# compteur_modifie_essence.net
KiCad netlist of a schematic drawn in EAGLE
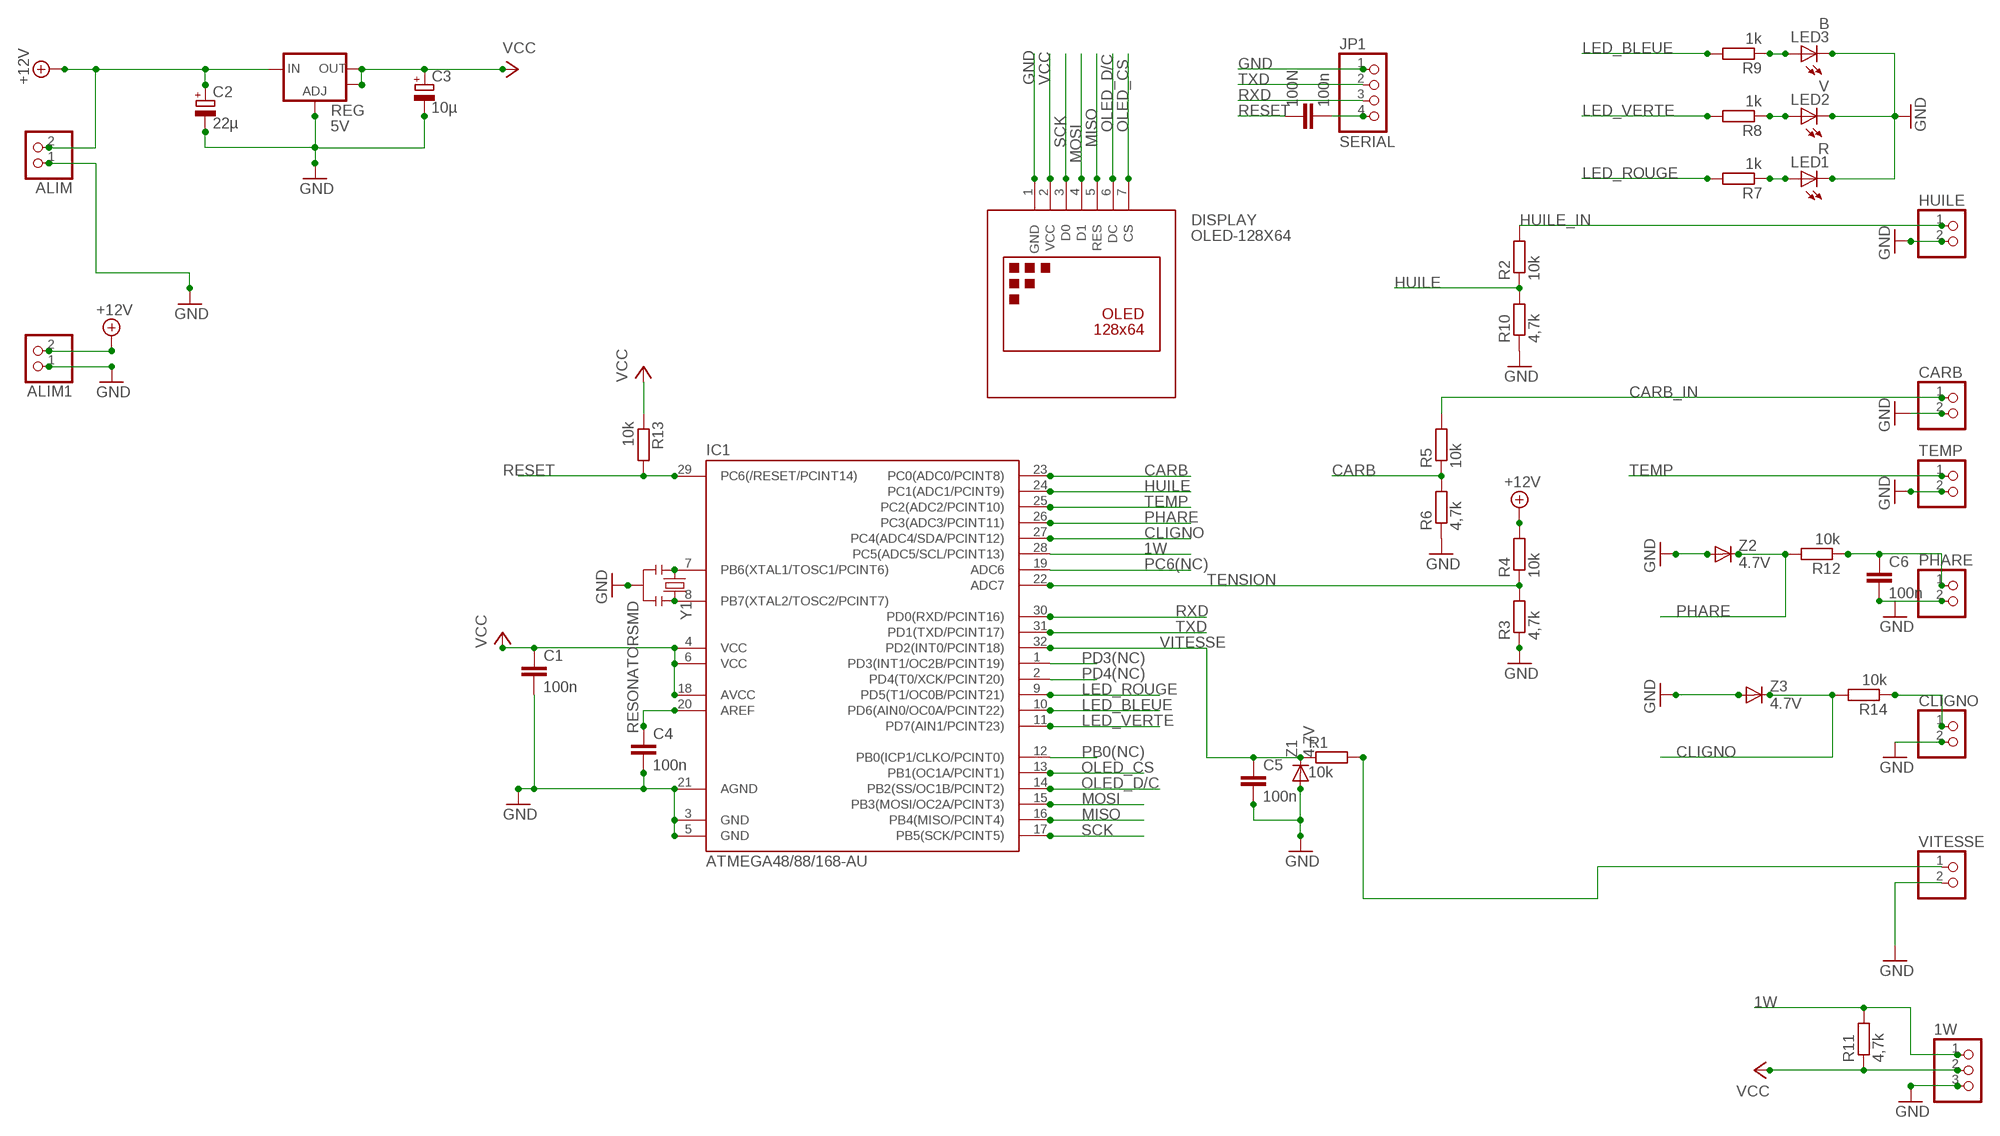
[diagram p0: schematic, sheet 1]

(export (version "E")
  (design (tool "Eeschema 10.0.6"))
  (components
    (comp (ref "1W")
      (value "PINHD-1X3CB")
      (footprint "eagle-import:1X03-CLEANBIG")
      (libsource (lib "eagle-import") (part "PINHD-1X3CB"))
    )
    (comp (ref "100N")
      (value "100n")
      (footprint "eagle-import:C1206")
      (libsource (lib "eagle-import") (part "C-EUC1206"))
    )
    (comp (ref "ALIM")
      (value "PINHD-1X2")
      (footprint "eagle-import:1X02")
      (libsource (lib "eagle-import") (part "PINHD-1X2"))
    )
    (comp (ref "ALIM1")
      (value "PINHD-1X2")
      (footprint "eagle-import:1X02")
      (libsource (lib "eagle-import") (part "PINHD-1X2"))
    )
    (comp (ref "C1")
      (value "100n")
      (footprint "eagle-import:C1206")
      (libsource (lib "eagle-import") (part "C-EUC1206"))
    )
    (comp (ref "C2")
      (value "22µ")
      (footprint "eagle-import:SMC_D")
      (libsource (lib "eagle-import") (part "resistor_CPOL-EUSMCD"))
    )
    (comp (ref "C3")
      (value "10µ")
      (footprint "eagle-import:SMC_C")
      (libsource (lib "eagle-import") (part "CPOL-EUSMCC"))
    )
    (comp (ref "C4")
      (value "100n")
      (footprint "eagle-import:C1206")
      (libsource (lib "eagle-import") (part "C-EUC1206"))
    )
    (comp (ref "C5")
      (value "100n")
      (footprint "eagle-import:C1206")
      (libsource (lib "eagle-import") (part "C-EUC1206"))
    )
    (comp (ref "C6")
      (value "100n")
      (footprint "eagle-import:C1206")
      (libsource (lib "eagle-import") (part "C-EUC1206"))
    )
    (comp (ref "CARB")
      (value "PINHD-1X2")
      (footprint "eagle-import:1X02")
      (libsource (lib "eagle-import") (part "PINHD-1X2"))
    )
    (comp (ref "CLIGNO")
      (value "PINHD-1X2")
      (footprint "eagle-import:1X02")
      (libsource (lib "eagle-import") (part "PINHD-1X2"))
    )
    (comp (ref "DISPLAY")
      (value "OLED-128X64")
      (footprint "eagle-import:DISPLAY-OLED-128X64")
      (libsource (lib "eagle-import") (part "DISPLAY-OLED-128X64"))
    )
    (comp (ref "HUILE")
      (value "PINHD-1X2")
      (footprint "eagle-import:1X02")
      (libsource (lib "eagle-import") (part "PINHD-1X2"))
    )
    (comp (ref "IC1")
      (value "ATMEGA48/88/168-AU")
      (footprint "eagle-import:TQFP32-08")
      (libsource (lib "eagle-import") (part "ATMEGA48/88/168-AU"))
    )
    (comp (ref "JP1")
      (value "SERIAL")
      (footprint "eagle-import:1X04_ROUND")
      (libsource (lib "eagle-import") (part "HEADER-1X4ROUND"))
    )
    (comp (ref "LED1")
      (value "R")
      (footprint "eagle-import:LED5MM")
      (libsource (lib "eagle-import") (part "LED5MM"))
    )
    (comp (ref "LED2")
      (value "V")
      (footprint "eagle-import:LED5MM")
      (libsource (lib "eagle-import") (part "LED5MM"))
    )
    (comp (ref "LED3")
      (value "B")
      (footprint "eagle-import:LED5MM")
      (libsource (lib "eagle-import") (part "LED5MM"))
    )
    (comp (ref "PHARE")
      (value "PINHD-1X2")
      (footprint "eagle-import:1X02")
      (libsource (lib "eagle-import") (part "PINHD-1X2"))
    )
    (comp (ref "R1")
      (value "10k")
      (footprint "eagle-import:R1206")
      (libsource (lib "eagle-import") (part "R-EU_R1206"))
    )
    (comp (ref "R2")
      (value "10k")
      (footprint "eagle-import:R1206")
      (libsource (lib "eagle-import") (part "R-EU_R1206"))
    )
    (comp (ref "R3")
      (value "4,7k")
      (footprint "eagle-import:R1206")
      (libsource (lib "eagle-import") (part "R-EU_R1206"))
    )
    (comp (ref "R4")
      (value "10k")
      (footprint "eagle-import:R1206")
      (libsource (lib "eagle-import") (part "R-EU_R1206"))
    )
    (comp (ref "R5")
      (value "10k")
      (footprint "eagle-import:R1206")
      (libsource (lib "eagle-import") (part "R-EU_R1206"))
    )
    (comp (ref "R6")
      (value "4,7k")
      (footprint "eagle-import:R1206")
      (libsource (lib "eagle-import") (part "R-EU_R1206"))
    )
    (comp (ref "R7")
      (value "1k")
      (footprint "eagle-import:R1206")
      (libsource (lib "eagle-import") (part "R-EU_R1206"))
    )
    (comp (ref "R8")
      (value "1k")
      (footprint "eagle-import:R1206")
      (libsource (lib "eagle-import") (part "R-EU_R1206"))
    )
    (comp (ref "R9")
      (value "1k")
      (footprint "eagle-import:R1206")
      (libsource (lib "eagle-import") (part "R-EU_R1206"))
    )
    (comp (ref "R10")
      (value "4,7k")
      (footprint "eagle-import:R1206")
      (libsource (lib "eagle-import") (part "R-EU_R1206"))
    )
    (comp (ref "R11")
      (value "4,7k")
      (footprint "eagle-import:R1206")
      (libsource (lib "eagle-import") (part "R-EU_R1206"))
    )
    (comp (ref "R12")
      (value "10k")
      (footprint "eagle-import:R1206")
      (libsource (lib "eagle-import") (part "R-EU_R1206"))
    )
    (comp (ref "R13")
      (value "10k")
      (footprint "eagle-import:R1206")
      (libsource (lib "eagle-import") (part "R-EU_R1206"))
    )
    (comp (ref "R14")
      (value "10k")
      (footprint "eagle-import:R1206")
      (libsource (lib "eagle-import") (part "R-EU_R1206"))
    )
    (comp (ref "REG")
      (value "5V")
      (footprint "eagle-import:SOT223")
      (libsource (lib "eagle-import") (part "V_REG_LM1117SOT223"))
    )
    (comp (ref "TEMP")
      (value "PINHD-1X2")
      (footprint "eagle-import:1X02")
      (libsource (lib "eagle-import") (part "PINHD-1X2"))
    )
    (comp (ref "VITESSE")
      (value "PINHD-1X2")
      (footprint "eagle-import:1X02")
      (libsource (lib "eagle-import") (part "PINHD-1X2"))
    )
    (comp (ref "Y1")
      (value "RESONATORSMD")
      (footprint "eagle-import:RESONATOR-SMD")
      (libsource (lib "eagle-import") (part "RESONATORSMD"))
    )
    (comp (ref "Z1")
      (value "4.7V")
      (footprint "eagle-import:SOD123")
      (libsource (lib "eagle-import") (part "DIODE-SOD123"))
    )
    (comp (ref "Z2")
      (value "4.7V")
      (footprint "eagle-import:SOD123")
      (libsource (lib "eagle-import") (part "DIODE-SOD123"))
    )
    (comp (ref "Z3")
      (value "4.7V")
      (footprint "eagle-import:SOD123")
      (libsource (lib "eagle-import") (part "DIODE-SOD123"))
    )
  )
  (nets
    (net (code "1") (name "+12V") (class "Default")
      (node (ref "ALIM") (pin "2") (pinfunction "2_2") (pintype "passive"))
      (node (ref "ALIM1") (pin "2") (pinfunction "2_2") (pintype "passive"))
      (node (ref "C2") (pin "+") (pinfunction "+_+") (pintype "passive"))
      (node (ref "R4") (pin "2") (pinfunction "2_2") (pintype "passive"))
      (node (ref "REG") (pin "3") (pinfunction "IN_3") (pintype "input"))
    )
    (net (code "2") (name "/1W") (class "Default")
      (node (ref "1W") (pin "1") (pinfunction "1_1") (pintype "passive"))
      (node (ref "IC1") (pin "28") (pinfunction "PC5(ADC5/SCL/PCINT13)_28") (pintype "bidirectional"))
      (node (ref "R11") (pin "2") (pinfunction "2_2") (pintype "passive"))
    )
    (net (code "3") (name "/CARB") (class "Default")
      (node (ref "IC1") (pin "23") (pinfunction "PC0(ADC0/PCINT8)_23") (pintype "bidirectional"))
      (node (ref "R5") (pin "1") (pinfunction "1_1") (pintype "passive"))
      (node (ref "R6") (pin "2") (pinfunction "2_2") (pintype "passive"))
    )
    (net (code "4") (name "/CARB_IN") (class "Default")
      (node (ref "CARB") (pin "1") (pinfunction "1_1") (pintype "passive"))
      (node (ref "R5") (pin "2") (pinfunction "2_2") (pintype "passive"))
    )
    (net (code "5") (name "/CLIGNO") (class "Default")
      (node (ref "IC1") (pin "27") (pinfunction "PC4(ADC4/SDA/PCINT12)_27") (pintype "bidirectional"))
      (node (ref "R14") (pin "2") (pinfunction "2_2") (pintype "passive"))
      (node (ref "Z3") (pin "C") (pinfunction "C_C") (pintype "passive"))
    )
    (net (code "6") (name "/HUILE") (class "Default")
      (node (ref "IC1") (pin "24") (pinfunction "PC1(ADC1/PCINT9)_24") (pintype "bidirectional"))
      (node (ref "R10") (pin "2") (pinfunction "2_2") (pintype "passive"))
      (node (ref "R2") (pin "1") (pinfunction "1_1") (pintype "passive"))
    )
    (net (code "7") (name "/HUILE_IN") (class "Default")
      (node (ref "HUILE") (pin "1") (pinfunction "1_1") (pintype "passive"))
      (node (ref "R2") (pin "2") (pinfunction "2_2") (pintype "passive"))
    )
    (net (code "8") (name "/LED_BLEUE") (class "Default")
      (node (ref "IC1") (pin "10") (pinfunction "PD6(AIN0/OC0A/PCINT22)_10") (pintype "bidirectional"))
      (node (ref "R9") (pin "2") (pinfunction "2_2") (pintype "passive"))
    )
    (net (code "9") (name "/LED_ROUGE") (class "Default")
      (node (ref "IC1") (pin "9") (pinfunction "PD5(T1/OC0B/PCINT21)_9") (pintype "bidirectional"))
      (node (ref "R7") (pin "2") (pinfunction "2_2") (pintype "passive"))
    )
    (net (code "10") (name "/LED_VERTE") (class "Default")
      (node (ref "IC1") (pin "11") (pinfunction "PD7(AIN1/PCINT23)_11") (pintype "bidirectional"))
      (node (ref "R8") (pin "2") (pinfunction "2_2") (pintype "passive"))
    )
    (net (code "11") (name "/MISO") (class "Default")
      (node (ref "DISPLAY") (pin "5") (pinfunction "RES_5") (pintype "bidirectional"))
      (node (ref "IC1") (pin "16") (pinfunction "PB4(MISO/PCINT4)_16") (pintype "bidirectional"))
    )
    (net (code "12") (name "/MOSI") (class "Default")
      (node (ref "DISPLAY") (pin "4") (pinfunction "D1_4") (pintype "bidirectional"))
      (node (ref "IC1") (pin "15") (pinfunction "PB3(MOSI/OC2A/PCINT3)_15") (pintype "bidirectional"))
    )
    (net (code "13") (name "/OLED_CS") (class "Default")
      (node (ref "DISPLAY") (pin "7") (pinfunction "CS_7") (pintype "bidirectional"))
      (node (ref "IC1") (pin "13") (pinfunction "PB1(OC1A/PCINT1)_13") (pintype "bidirectional"))
    )
    (net (code "14") (name "/OLED_D{slash}C") (class "Default")
      (node (ref "DISPLAY") (pin "6") (pinfunction "DC_6") (pintype "bidirectional"))
      (node (ref "IC1") (pin "14") (pinfunction "PB2(SS/OC1B/PCINT2)_14") (pintype "bidirectional"))
    )
    (net (code "15") (name "/PB0(NC)") (class "Default")
      (node (ref "IC1") (pin "12") (pinfunction "PB0(ICP1/CLKO/PCINT0)_12") (pintype "bidirectional"))
    )
    (net (code "16") (name "/PC6(NC)") (class "Default")
      (node (ref "IC1") (pin "19") (pinfunction "ADC6_19") (pintype "passive"))
    )
    (net (code "17") (name "/PD3(NC)") (class "Default")
      (node (ref "IC1") (pin "1") (pinfunction "PD3(INT1/OC2B/PCINT19)_1") (pintype "bidirectional"))
    )
    (net (code "18") (name "/PD4(NC)") (class "Default")
      (node (ref "IC1") (pin "2") (pinfunction "PD4(T0/XCK/PCINT20)_2") (pintype "bidirectional"))
    )
    (net (code "19") (name "/PHARE") (class "Default")
      (node (ref "IC1") (pin "26") (pinfunction "PC3(ADC3/PCINT11)_26") (pintype "bidirectional"))
      (node (ref "R12") (pin "2") (pinfunction "2_2") (pintype "passive"))
      (node (ref "Z2") (pin "C") (pinfunction "C_C") (pintype "passive"))
    )
    (net (code "20") (name "/RESET") (class "Default")
      (node (ref "100N") (pin "1") (pinfunction "1_1") (pintype "passive"))
      (node (ref "IC1") (pin "29") (pinfunction "PC6(/RESET/PCINT14)_29") (pintype "bidirectional"))
      (node (ref "R13") (pin "2") (pinfunction "2_2") (pintype "passive"))
    )
    (net (code "21") (name "/RXD") (class "Default")
      (node (ref "IC1") (pin "30") (pinfunction "PD0(RXD/PCINT16)_30") (pintype "bidirectional"))
      (node (ref "JP1") (pin "3") (pinfunction "3_3") (pintype "passive"))
    )
    (net (code "22") (name "/SCK") (class "Default")
      (node (ref "DISPLAY") (pin "3") (pinfunction "D0_3") (pintype "bidirectional"))
      (node (ref "IC1") (pin "17") (pinfunction "PB5(SCK/PCINT5)_17") (pintype "bidirectional"))
    )
    (net (code "23") (name "/TEMP") (class "Default")
      (node (ref "IC1") (pin "25") (pinfunction "PC2(ADC2/PCINT10)_25") (pintype "bidirectional"))
      (node (ref "TEMP") (pin "1") (pinfunction "1_1") (pintype "passive"))
    )
    (net (code "24") (name "/TENSION") (class "Default")
      (node (ref "IC1") (pin "22") (pinfunction "ADC7_22") (pintype "passive"))
      (node (ref "R3") (pin "2") (pinfunction "2_2") (pintype "passive"))
      (node (ref "R4") (pin "1") (pinfunction "1_1") (pintype "passive"))
    )
    (net (code "25") (name "/TXD") (class "Default")
      (node (ref "IC1") (pin "31") (pinfunction "PD1(TXD/PCINT17)_31") (pintype "bidirectional"))
      (node (ref "JP1") (pin "2") (pinfunction "2_2") (pintype "passive"))
    )
    (net (code "26") (name "/VITESSE") (class "Default")
      (node (ref "C5") (pin "1") (pinfunction "1_1") (pintype "passive"))
      (node (ref "IC1") (pin "32") (pinfunction "PD2(INT0/PCINT18)_32") (pintype "bidirectional"))
      (node (ref "R1") (pin "1") (pinfunction "1_1") (pintype "passive"))
      (node (ref "Z1") (pin "C") (pinfunction "C_C") (pintype "passive"))
    )
    (net (code "27") (name "GND") (class "Default")
      (node (ref "1W") (pin "3") (pinfunction "3_3") (pintype "passive"))
      (node (ref "ALIM") (pin "1") (pinfunction "1_1") (pintype "passive"))
      (node (ref "ALIM1") (pin "1") (pinfunction "1_1") (pintype "passive"))
      (node (ref "C1") (pin "2") (pinfunction "2_2") (pintype "passive"))
      (node (ref "C2") (pin "-") (pinfunction "-_-") (pintype "passive"))
      (node (ref "C3") (pin "-") (pinfunction "-_-") (pintype "passive"))
      (node (ref "C4") (pin "2") (pinfunction "2_2") (pintype "passive"))
      (node (ref "C5") (pin "2") (pinfunction "2_2") (pintype "passive"))
      (node (ref "C6") (pin "2") (pinfunction "2_2") (pintype "passive"))
      (node (ref "CARB") (pin "2") (pinfunction "2_2") (pintype "passive"))
      (node (ref "CLIGNO") (pin "2") (pinfunction "2_2") (pintype "passive"))
      (node (ref "DISPLAY") (pin "1") (pinfunction "GND_1") (pintype "power_in"))
      (node (ref "HUILE") (pin "2") (pinfunction "2_2") (pintype "passive"))
      (node (ref "IC1") (pin "21") (pinfunction "AGND_21") (pintype "power_in"))
      (node (ref "IC1") (pin "3") (pinfunction "GND_3") (pintype "power_in"))
      (node (ref "IC1") (pin "5") (pinfunction "GND_5") (pintype "power_in"))
      (node (ref "JP1") (pin "1") (pinfunction "1_1") (pintype "passive"))
      (node (ref "LED1") (pin "K") (pinfunction "C_K") (pintype "passive"))
      (node (ref "LED2") (pin "K") (pinfunction "C_K") (pintype "passive"))
      (node (ref "LED3") (pin "K") (pinfunction "C_K") (pintype "passive"))
      (node (ref "PHARE") (pin "2") (pinfunction "2_2") (pintype "passive"))
      (node (ref "R10") (pin "1") (pinfunction "1_1") (pintype "passive"))
      (node (ref "R3") (pin "1") (pinfunction "1_1") (pintype "passive"))
      (node (ref "R6") (pin "1") (pinfunction "1_1") (pintype "passive"))
      (node (ref "REG") (pin "1") (pinfunction "ADJ_1") (pintype "input"))
      (node (ref "TEMP") (pin "2") (pinfunction "2_2") (pintype "passive"))
      (node (ref "VITESSE") (pin "2") (pinfunction "2_2") (pintype "passive"))
      (node (ref "Y1") (pin "2") (pinfunction "2_2") (pintype "passive"))
      (node (ref "Z1") (pin "A") (pinfunction "A_A") (pintype "passive"))
      (node (ref "Z2") (pin "A") (pinfunction "A_A") (pintype "passive"))
      (node (ref "Z3") (pin "A") (pinfunction "A_A") (pintype "passive"))
    )
    (net (code "28") (name "Net-(100N-Pad2)") (class "Default")
      (node (ref "100N") (pin "2") (pinfunction "2_2") (pintype "passive"))
      (node (ref "JP1") (pin "4") (pinfunction "4_4") (pintype "passive"))
    )
    (net (code "29") (name "Net-(C6-Pad1)") (class "Default")
      (node (ref "C6") (pin "1") (pinfunction "1_1") (pintype "passive"))
      (node (ref "PHARE") (pin "1") (pinfunction "1_1") (pintype "passive"))
      (node (ref "R12") (pin "1") (pinfunction "1_1") (pintype "passive"))
    )
    (net (code "30") (name "Net-(CLIGNO-Pad1)") (class "Default")
      (node (ref "CLIGNO") (pin "1") (pinfunction "1_1") (pintype "passive"))
      (node (ref "R14") (pin "1") (pinfunction "1_1") (pintype "passive"))
    )
    (net (code "31") (name "Net-(IC1-AREF)") (class "Default")
      (node (ref "C4") (pin "1") (pinfunction "1_1") (pintype "passive"))
      (node (ref "IC1") (pin "20") (pinfunction "AREF_20") (pintype "passive"))
    )
    (net (code "32") (name "Net-(IC1-PB6(XTAL1{slash}TOSC1{slash}PCINT6))") (class "Default")
      (node (ref "IC1") (pin "7") (pinfunction "PB6(XTAL1/TOSC1/PCINT6)_7") (pintype "bidirectional"))
      (node (ref "Y1") (pin "1") (pinfunction "1_1") (pintype "passive"))
    )
    (net (code "33") (name "Net-(IC1-PB7(XTAL2{slash}TOSC2{slash}PCINT7))") (class "Default")
      (node (ref "IC1") (pin "8") (pinfunction "PB7(XTAL2/TOSC2/PCINT7)_8") (pintype "bidirectional"))
      (node (ref "Y1") (pin "3") (pinfunction "3_3") (pintype "passive"))
    )
    (net (code "34") (name "Net-(LED1-PadA)") (class "Default")
      (node (ref "LED1") (pin "A") (pinfunction "A_A") (pintype "passive"))
      (node (ref "R7") (pin "1") (pinfunction "1_1") (pintype "passive"))
    )
    (net (code "35") (name "Net-(LED2-PadA)") (class "Default")
      (node (ref "LED2") (pin "A") (pinfunction "A_A") (pintype "passive"))
      (node (ref "R8") (pin "1") (pinfunction "1_1") (pintype "passive"))
    )
    (net (code "36") (name "Net-(LED3-PadA)") (class "Default")
      (node (ref "LED3") (pin "A") (pinfunction "A_A") (pintype "passive"))
      (node (ref "R9") (pin "1") (pinfunction "1_1") (pintype "passive"))
    )
    (net (code "37") (name "Net-(R1-Pad2)") (class "Default")
      (node (ref "R1") (pin "2") (pinfunction "2_2") (pintype "passive"))
      (node (ref "VITESSE") (pin "1") (pinfunction "1_1") (pintype "passive"))
    )
    (net (code "38") (name "VCC") (class "Default")
      (node (ref "1W") (pin "2") (pinfunction "2_2") (pintype "passive"))
      (node (ref "C1") (pin "1") (pinfunction "1_1") (pintype "passive"))
      (node (ref "C3") (pin "+") (pinfunction "+_+") (pintype "passive"))
      (node (ref "DISPLAY") (pin "2") (pinfunction "VCC_2") (pintype "power_in"))
      (node (ref "IC1") (pin "18") (pinfunction "AVCC_18") (pintype "passive"))
      (node (ref "IC1") (pin "4") (pinfunction "VCC_4") (pintype "power_in"))
      (node (ref "IC1") (pin "6") (pinfunction "VCC_6") (pintype "power_in"))
      (node (ref "R11") (pin "1") (pinfunction "1_1") (pintype "passive"))
      (node (ref "R13") (pin "1") (pinfunction "1_1") (pintype "passive"))
      (node (ref "REG") (pin "2") (pinfunction "OUT_2") (pintype "output"))
      (node (ref "REG") (pin "4") (pinfunction "OUT_4") (pintype "output"))
    )
  )
)
